# Sheet1.net
KiCad netlist of a schematic drawn in Altium Designer
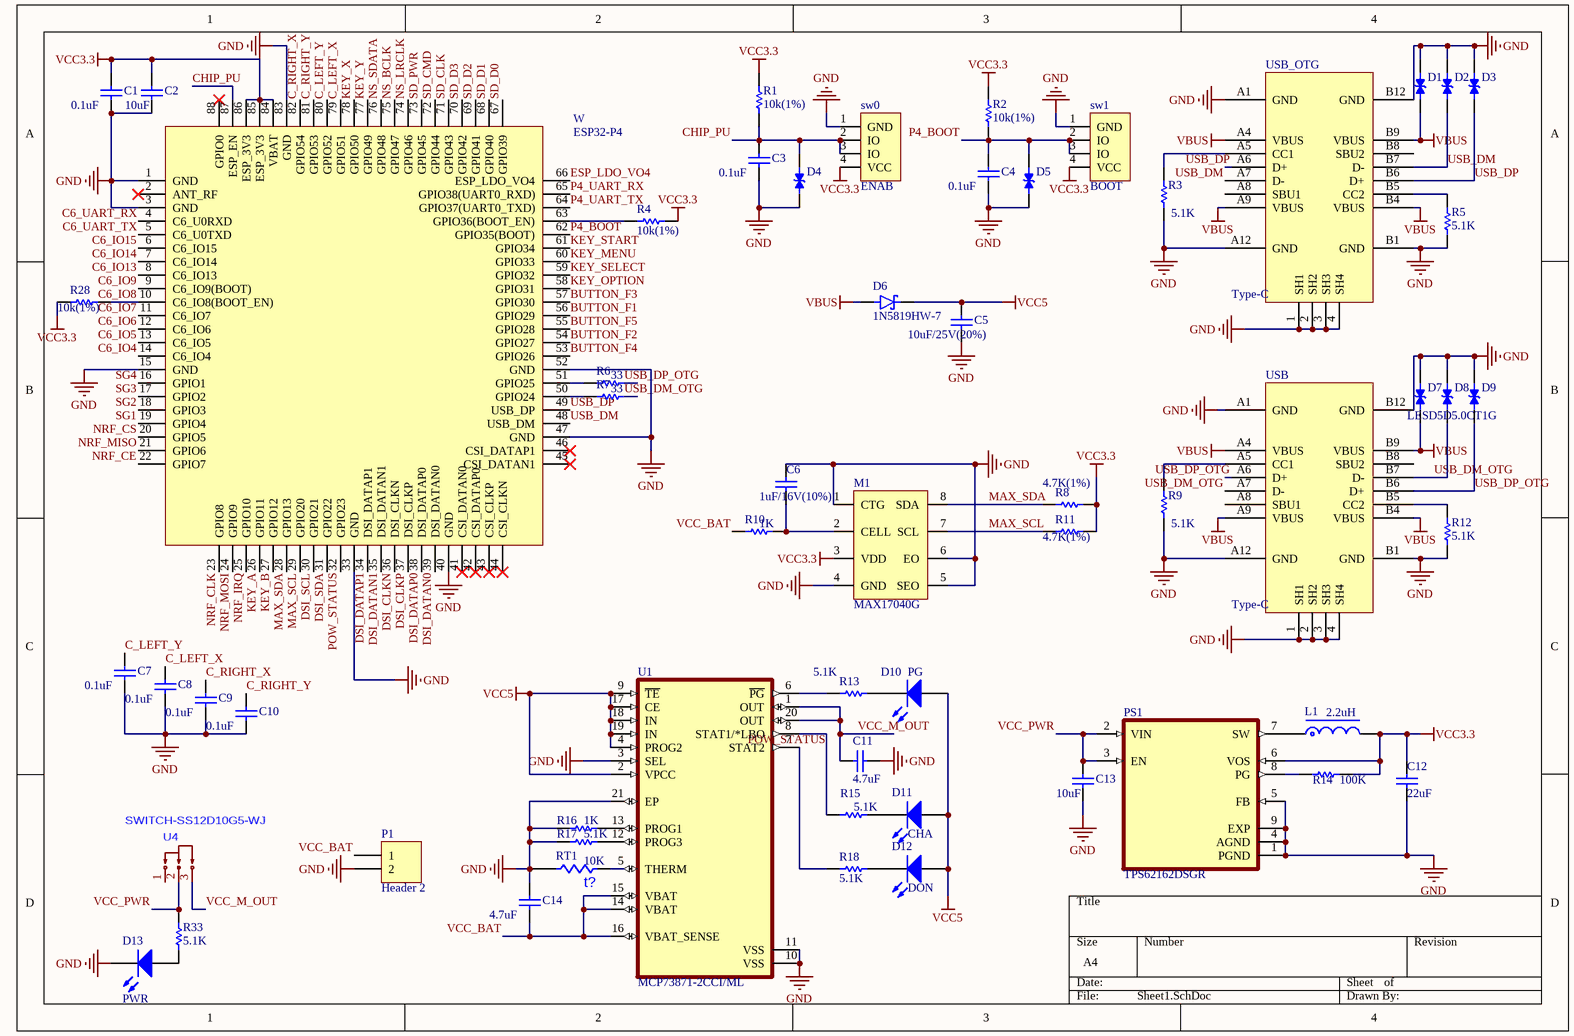
[diagram p0: Sheet1.SchDoc]

(export (version "E")
  (design (tool "Eeschema 10.0.6"))
  (components
    (comp (ref "C1")
      (value "0.1uF")
      (footprint "C0805")
      (description "Capacitor")
      (fields (field (name "Comment") "0.1uF/50V(10%)") (field (name "PUBLISHER") "Altium Limited"))
      (libsource (lib "Miscellaneous Devices") (part "Cap"))
    )
    (comp (ref "C2")
      (value "10uF")
      (footprint "C0805")
      (description "Capacitor")
      (fields (field (name "PUBLISHER") "Altium Limited"))
      (libsource (lib "Miscellaneous Devices") (part "Cap"))
    )
    (comp (ref "C3")
      (value "0.1uF")
      (footprint "C0805")
      (description "Capacitor")
      (fields (field (name "Comment") "0.1uF/50V(10%)") (field (name "PUBLISHER") "Altium Limited"))
      (libsource (lib "Miscellaneous Devices") (part "Cap"))
    )
    (comp (ref "C4")
      (value "0.1uF")
      (footprint "C0805")
      (description "Capacitor")
      (fields (field (name "Comment") "0.1uF/50V(10%)") (field (name "PUBLISHER") "Altium Limited"))
      (libsource (lib "Miscellaneous Devices") (part "Cap"))
    )
    (comp (ref "C5")
      (value "10uF/25V(20%)")
      (footprint "C0805")
      (description "Capacitor")
      (fields (field (name "PUBLISHER") "Altium Limited"))
      (libsource (lib "Miscellaneous Devices") (part "Cap"))
    )
    (comp (ref "C6")
      (value "1uF/16V(10%)")
      (footprint "C0805")
      (description "Capacitor")
      (fields (field (name "PUBLISHER") "Altium Limited"))
      (libsource (lib "Miscellaneous Devices") (part "Cap"))
    )
    (comp (ref "C7")
      (value "0.1uF")
      (footprint "C0805")
      (description "Capacitor")
      (fields (field (name "Comment") "0.1uF/50V(10%)") (field (name "PUBLISHER") "Altium Limited"))
      (libsource (lib "Miscellaneous Devices") (part "Cap"))
    )
    (comp (ref "C8")
      (value "0.1uF")
      (footprint "C0805")
      (description "Capacitor")
      (fields (field (name "Comment") "0.1uF/50V(10%)") (field (name "PUBLISHER") "Altium Limited"))
      (libsource (lib "Miscellaneous Devices") (part "Cap"))
    )
    (comp (ref "C9")
      (value "0.1uF")
      (footprint "C0805")
      (description "Capacitor")
      (fields (field (name "Comment") "0.1uF/50V(10%)") (field (name "PUBLISHER") "Altium Limited"))
      (libsource (lib "Miscellaneous Devices") (part "Cap"))
    )
    (comp (ref "C10")
      (value "0.1uF")
      (footprint "C0805")
      (description "Capacitor")
      (fields (field (name "Comment") "0.1uF/50V(10%)") (field (name "PUBLISHER") "Altium Limited"))
      (libsource (lib "Miscellaneous Devices") (part "Cap"))
    )
    (comp (ref "C11")
      (value "4.7uF")
      (footprint "C0805")
      (description "Capacitor")
      (fields (field (name "PUBLISHER") "Altium Limited"))
      (libsource (lib "Miscellaneous Devices") (part "Cap"))
    )
    (comp (ref "C12")
      (value "22uF")
      (footprint "C0805")
      (description "Capacitor")
      (fields (field (name "PUBLISHER") "Altium Limited"))
      (libsource (lib "Miscellaneous Devices") (part "Cap"))
    )
    (comp (ref "C13")
      (value "10uF")
      (footprint "C0805")
      (description "Capacitor")
      (fields (field (name "PUBLISHER") "Altium Limited"))
      (libsource (lib "Miscellaneous Devices") (part "Cap"))
    )
    (comp (ref "C14")
      (value "4.7uF")
      (footprint "C0805")
      (description "Capacitor")
      (fields (field (name "PUBLISHER") "Altium Limited"))
      (libsource (lib "Miscellaneous Devices") (part "Cap"))
    )
    (comp (ref "D1")
      (value "~")
      (footprint "TVS_LESD5D5.0CT1G")
      (description "Transient Voltage Suppressors for ESD Protection")
      (fields (field (name "MF") "Leshan Radio Co.") (field (name "MP") "LESD5D5.0CT1G"))
      (libsource (lib "welkin_lib_v1.0") (part "LESD5D5.0CT1G"))
    )
    (comp (ref "D2")
      (value "~")
      (footprint "TVS_LESD5D5.0CT1G")
      (description "Transient Voltage Suppressors for ESD Protection")
      (fields (field (name "MF") "Leshan Radio Co.") (field (name "MP") "LESD5D5.0CT1G"))
      (libsource (lib "welkin_lib_v1.0") (part "LESD5D5.0CT1G"))
    )
    (comp (ref "D3")
      (value "~")
      (footprint "TVS_LESD5D5.0CT1G")
      (description "Transient Voltage Suppressors for ESD Protection")
      (fields (field (name "MF") "Leshan Radio Co.") (field (name "MP") "LESD5D5.0CT1G"))
      (libsource (lib "welkin_lib_v1.0") (part "LESD5D5.0CT1G"))
    )
    (comp (ref "D4")
      (value "~")
      (footprint "TVS_LESD5D5.0CT1G")
      (description "Transient Voltage Suppressors for ESD Protection")
      (fields (field (name "MF") "Leshan Radio Co.") (field (name "MP") "LESD5D5.0CT1G"))
      (libsource (lib "welkin_lib_v1.0") (part "LESD5D5.0CT1G"))
    )
    (comp (ref "D5")
      (value "~")
      (footprint "TVS_LESD5D5.0CT1G")
      (description "Transient Voltage Suppressors for ESD Protection")
      (fields (field (name "MF") "Leshan Radio Co.") (field (name "MP") "LESD5D5.0CT1G"))
      (libsource (lib "welkin_lib_v1.0") (part "LESD5D5.0CT1G"))
    )
    (comp (ref "D6")
      (value "1N5819HW-7")
      (footprint "SOD3715X145N")
      (description "Diode Schottky 40 V 1A Surface Mount SOD-123")
      (fields (field (name "MF") "Diodes Inc."))
      (libsource (lib "Schlib1") (part "1N5819HW-7"))
    )
    (comp (ref "D7")
      (value "~")
      (footprint "TVS_LESD5D5.0CT1G")
      (description "Transient Voltage Suppressors for ESD Protection")
      (fields (field (name "MF") "Leshan Radio Co.") (field (name "MP") "LESD5D5.0CT1G"))
      (libsource (lib "welkin_lib_v1.0") (part "LESD5D5.0CT1G"))
    )
    (comp (ref "D8")
      (value "LESD5D5.0CT1G")
      (footprint "TVS_LESD5D5.0CT1G")
      (description "Transient Voltage Suppressors for ESD Protection")
      (fields (field (name "MF") "Leshan Radio Co."))
      (libsource (lib "welkin_lib_v1.0") (part "LESD5D5.0CT1G"))
    )
    (comp (ref "D9")
      (value "~")
      (footprint "TVS_LESD5D5.0CT1G")
      (description "Transient Voltage Suppressors for ESD Protection")
      (fields (field (name "MF") "Leshan Radio Co.") (field (name "MP") "LESD5D5.0CT1G"))
      (libsource (lib "welkin_lib_v1.0") (part "LESD5D5.0CT1G"))
    )
    (comp (ref "D10")
      (value "PG")
      (footprint "C0805")
      (description "Typical INFRARED GaAs LED")
      (fields (field (name "PUBLISHER") "Altium Limited"))
      (libsource (lib "Miscellaneous Devices") (part "LED0"))
    )
    (comp (ref "D11")
      (value "CHA")
      (footprint "C0805")
      (description "Typical INFRARED GaAs LED")
      (fields (field (name "PUBLISHER") "Altium Limited"))
      (libsource (lib "Miscellaneous Devices") (part "LED0"))
    )
    (comp (ref "D12")
      (value "DON")
      (footprint "C0805")
      (description "Typical INFRARED GaAs LED")
      (fields (field (name "PUBLISHER") "Altium Limited"))
      (libsource (lib "Miscellaneous Devices") (part "LED0"))
    )
    (comp (ref "D13")
      (value "PWR")
      (footprint "C0805")
      (description "Typical INFRARED GaAs LED")
      (fields (field (name "PUBLISHER") "Altium Limited"))
      (libsource (lib "Miscellaneous Devices") (part "LED0"))
    )
    (comp (ref "L1")
      (value "2.2uH")
      (footprint "INDC6060X300")
      (description "NR功率电感")
      (fields (field (name "版权归属") "源创客"))
      (libsource (lib "welkin_lib_v1.0") (part "L-NR"))
    )
    (comp (ref "M1")
      (value "MAX17040G")
      (footprint "MAX17040G+T")
      (description "电量检测")
      (libsource (lib "Schlib1") (part "MAX17040G"))
    )
    (comp (ref "P1")
      (value "Header 2")
      (footprint "XH2.54-2P")
      (description "Header, 2-Pin")
      (fields (field (name "PUBLISHER") "Altium Limited"))
      (libsource (lib "Miscellaneous Connectors") (part "Header 2"))
    )
    (comp (ref "PS1")
      (value "TPS62162DSGR")
      (footprint "TPS62162DSGR")
      (description "3V-17V 1A Step-Down Converters with DCS-Controlâ„¢")
      (fields (field (name "MF") "Texas Instruments"))
      (libsource (lib "welkin_lib_v1.0") (part "TPS62162DSGR"))
    )
    (comp (ref "R1")
      (value "10k(1%)")
      (footprint "C0805")
      (description "Resistor")
      (fields (field (name "PUBLISHER") "Altium Limited"))
      (libsource (lib "Miscellaneous Devices") (part "Res1"))
    )
    (comp (ref "R2")
      (value "10k(1%)")
      (footprint "C0805")
      (description "Resistor")
      (fields (field (name "PUBLISHER") "Altium Limited"))
      (libsource (lib "Miscellaneous Devices") (part "Res1"))
    )
    (comp (ref "R3")
      (value "5.1K")
      (footprint "C0805")
      (description "Resistor")
      (fields (field (name "PUBLISHER") "Altium Limited"))
      (libsource (lib "Miscellaneous Devices") (part "Res1"))
    )
    (comp (ref "R4")
      (value "10k(1%)")
      (footprint "C0805")
      (description "Resistor")
      (fields (field (name "PUBLISHER") "Altium Limited"))
      (libsource (lib "Miscellaneous Devices") (part "Res1"))
    )
    (comp (ref "R5")
      (value "5.1K")
      (footprint "C0805")
      (description "Resistor")
      (fields (field (name "PUBLISHER") "Altium Limited"))
      (libsource (lib "Miscellaneous Devices") (part "Res1"))
    )
    (comp (ref "R6")
      (value "33")
      (footprint "C0805")
      (description "Resistor")
      (fields (field (name "PUBLISHER") "Altium Limited"))
      (libsource (lib "Miscellaneous Devices") (part "Res1"))
    )
    (comp (ref "R7")
      (value "33")
      (footprint "C0805")
      (description "Resistor")
      (fields (field (name "PUBLISHER") "Altium Limited"))
      (libsource (lib "Miscellaneous Devices") (part "Res1"))
    )
    (comp (ref "R8")
      (value "4.7K(1%)")
      (footprint "C0805")
      (description "Resistor")
      (fields (field (name "PUBLISHER") "Altium Limited"))
      (libsource (lib "Miscellaneous Devices") (part "Res1"))
    )
    (comp (ref "R9")
      (value "5.1K")
      (footprint "C0805")
      (description "Resistor")
      (fields (field (name "PUBLISHER") "Altium Limited"))
      (libsource (lib "Miscellaneous Devices") (part "Res1"))
    )
    (comp (ref "R10")
      (value "1K")
      (footprint "C0805")
      (description "Resistor")
      (fields (field (name "PUBLISHER") "Altium Limited"))
      (libsource (lib "Miscellaneous Devices") (part "Res1"))
    )
    (comp (ref "R11")
      (value "4.7K(1%)")
      (footprint "C0805")
      (description "Resistor")
      (fields (field (name "PUBLISHER") "Altium Limited"))
      (libsource (lib "Miscellaneous Devices") (part "Res1"))
    )
    (comp (ref "R12")
      (value "5.1K")
      (footprint "C0805")
      (description "Resistor")
      (fields (field (name "PUBLISHER") "Altium Limited"))
      (libsource (lib "Miscellaneous Devices") (part "Res1"))
    )
    (comp (ref "R13")
      (value "5.1K")
      (footprint "C0805")
      (description "Resistor")
      (fields (field (name "PUBLISHER") "Altium Limited"))
      (libsource (lib "Miscellaneous Devices") (part "Res1"))
    )
    (comp (ref "R14")
      (value "100K")
      (footprint "C0805")
      (description "Resistor")
      (fields (field (name "PUBLISHER") "Altium Limited"))
      (libsource (lib "Miscellaneous Devices") (part "Res1"))
    )
    (comp (ref "R15")
      (value "5.1K")
      (footprint "C0805")
      (description "Resistor")
      (fields (field (name "PUBLISHER") "Altium Limited"))
      (libsource (lib "Miscellaneous Devices") (part "Res1"))
    )
    (comp (ref "R16")
      (value "1K")
      (footprint "C0805")
      (description "Resistor")
      (fields (field (name "PUBLISHER") "Altium Limited"))
      (libsource (lib "Miscellaneous Devices") (part "Res1"))
    )
    (comp (ref "R17")
      (value "5.1K")
      (footprint "C0805")
      (description "Resistor")
      (fields (field (name "PUBLISHER") "Altium Limited"))
      (libsource (lib "Miscellaneous Devices") (part "Res1"))
    )
    (comp (ref "R18")
      (value "5.1K")
      (footprint "C0805")
      (description "Resistor")
      (fields (field (name "PUBLISHER") "Altium Limited"))
      (libsource (lib "Miscellaneous Devices") (part "Res1"))
    )
    (comp (ref "R28")
      (value "10k(1%)")
      (footprint "C0805")
      (description "Resistor")
      (fields (field (name "PUBLISHER") "Altium Limited"))
      (libsource (lib "Miscellaneous Devices") (part "Res1"))
    )
    (comp (ref "R33")
      (value "5.1K")
      (footprint "C0805")
      (description "Resistor")
      (fields (field (name "PUBLISHER") "Altium Limited"))
      (libsource (lib "Miscellaneous Devices") (part "Res1"))
    )
    (comp (ref "RT1")
      (value "10K")
      (footprint "NTC")
      (fields (field (name "PUBLISHER") "Altium Limited"))
      (libsource (lib "Miscellaneous Devices") (part "Res Thermal"))
    )
    (comp (ref "sw0")
      (value "ENAB")
      (footprint "SWITH_Light")
      (libsource (lib "welkin_lib_v1.0") (part "SWITCH_LIGHT"))
    )
    (comp (ref "sw1")
      (value "BOOT")
      (footprint "SWITH_Light")
      (libsource (lib "welkin_lib_v1.0") (part "SWITCH_LIGHT"))
    )
    (comp (ref "U1")
      (value "MCP73871-2CCI/ML")
      (footprint "MCP73871")
      (description "Charger IC Lithium Ion/Polymer 20-QFN (4x4)")
      (fields (field (name "MF") "Microchip Technology"))
      (libsource (lib "welkin_lib_v1.0") (part "MCP73871-2CCI/ML"))
    )
    (comp (ref "U4")
      (value "SWITCH-SS12D10G5-WJ")
      (footprint "SW-TH_SS12D10G5")
      (libsource (lib "welkin_lib_v1.0") (part "SWITCH-SS12D10G5-WJ"))
    )
    (comp (ref "USB")
      (value "Type-C")
      (footprint "Type-C-TOP")
      (libsource (lib "Schlib1") (part "USB-Type-C-TOP"))
    )
    (comp (ref "USB_OTG")
      (value "Type-C")
      (footprint "Type-C-TOP")
      (libsource (lib "Schlib1") (part "USB-Type-C-TOP"))
    )
    (comp (ref "W")
      (value "ESP32-P4")
      (footprint "ESP32-P4_MODULE")
      (description "ESP32P4+ESP32C6")
      (libsource (lib "welkin_lib_v1.0") (part "ESP32-P4-Module"))
    )
  )
  (nets
    (net (code "1") (name "/BUTTON_F1") (class "Default")
      (node (ref "W") (pin "56") (pinfunction "GPIO29_56") (pintype "passive"))
    )
    (net (code "2") (name "/BUTTON_F2") (class "Default")
      (node (ref "W") (pin "54") (pinfunction "GPIO27_54") (pintype "passive"))
    )
    (net (code "3") (name "/BUTTON_F3") (class "Default")
      (node (ref "W") (pin "57") (pinfunction "GPIO30_57") (pintype "passive"))
    )
    (net (code "4") (name "/BUTTON_F4") (class "Default")
      (node (ref "W") (pin "53") (pinfunction "GPIO26_53") (pintype "passive"))
    )
    (net (code "5") (name "/BUTTON_F5") (class "Default")
      (node (ref "W") (pin "55") (pinfunction "GPIO28_55") (pintype "passive"))
    )
    (net (code "6") (name "/C6_IO4") (class "Default")
      (node (ref "W") (pin "14") (pinfunction "C6_IO4_14") (pintype "passive"))
    )
    (net (code "7") (name "/C6_IO5") (class "Default")
      (node (ref "W") (pin "13") (pinfunction "C6_IO5_13") (pintype "passive"))
    )
    (net (code "8") (name "/C6_IO6") (class "Default")
      (node (ref "W") (pin "12") (pinfunction "C6_IO6_12") (pintype "passive"))
    )
    (net (code "9") (name "/C6_IO7") (class "Default")
      (node (ref "W") (pin "11") (pinfunction "C6_IO7_11") (pintype "passive"))
    )
    (net (code "10") (name "/C6_IO8") (class "Default")
      (node (ref "R28") (pin "1") (pinfunction "1_1") (pintype "passive"))
      (node (ref "W") (pin "10") (pinfunction "C6_IO8(BOOT_EN)_10") (pintype "passive"))
    )
    (net (code "11") (name "/C6_IO9") (class "Default")
      (node (ref "W") (pin "9") (pinfunction "C6_IO9(BOOT)_9") (pintype "passive"))
    )
    (net (code "12") (name "/C6_IO13") (class "Default")
      (node (ref "W") (pin "8") (pinfunction "C6_IO13_8") (pintype "passive"))
    )
    (net (code "13") (name "/C6_IO14") (class "Default")
      (node (ref "W") (pin "7") (pinfunction "C6_IO14_7") (pintype "passive"))
    )
    (net (code "14") (name "/C6_IO15") (class "Default")
      (node (ref "W") (pin "6") (pinfunction "C6_IO15_6") (pintype "passive"))
    )
    (net (code "15") (name "/C6_UART_RX") (class "Default")
      (node (ref "W") (pin "4") (pinfunction "C6_U0RXD_4") (pintype "passive"))
    )
    (net (code "16") (name "/C6_UART_TX") (class "Default")
      (node (ref "W") (pin "5") (pinfunction "C6_U0TXD_5") (pintype "passive"))
    )
    (net (code "17") (name "/CHIP_PU") (class "Default")
      (node (ref "C3") (pin "2") (pinfunction "2_2") (pintype "passive"))
      (node (ref "D4") (pin "2") (pinfunction "2_2") (pintype "passive"))
      (node (ref "R1") (pin "1") (pinfunction "1_1") (pintype "passive"))
      (node (ref "W") (pin "87") (pinfunction "ESP_EN_87") (pintype "passive"))
      (node (ref "sw0") (pin "2") (pinfunction "IO_2") (pintype "passive"))
      (node (ref "sw0") (pin "3") (pinfunction "IO_3") (pintype "passive"))
    )
    (net (code "18") (name "/C_LEFT_X") (class "Default")
      (node (ref "C8") (pin "2") (pinfunction "2_2") (pintype "passive"))
      (node (ref "W") (pin "79") (pinfunction "GPIO51_79") (pintype "passive"))
    )
    (net (code "19") (name "/C_LEFT_Y") (class "Default")
      (node (ref "C7") (pin "2") (pinfunction "2_2") (pintype "passive"))
      (node (ref "W") (pin "80") (pinfunction "GPIO52_80") (pintype "passive"))
    )
    (net (code "20") (name "/C_RIGHT_X") (class "Default")
      (node (ref "C9") (pin "2") (pinfunction "2_2") (pintype "passive"))
      (node (ref "W") (pin "82") (pinfunction "GPIO54_82") (pintype "passive"))
    )
    (net (code "21") (name "/C_RIGHT_Y") (class "Default")
      (node (ref "C10") (pin "2") (pinfunction "2_2") (pintype "passive"))
      (node (ref "W") (pin "81") (pinfunction "GPIO53_81") (pintype "passive"))
    )
    (net (code "22") (name "/DSI_CLKN") (class "Default")
      (node (ref "W") (pin "36") (pinfunction "DSI_CLKN_36") (pintype "passive"))
    )
    (net (code "23") (name "/DSI_CLKP") (class "Default")
      (node (ref "W") (pin "37") (pinfunction "DSI_CLKP_37") (pintype "passive"))
    )
    (net (code "24") (name "/DSI_DATAN0") (class "Default")
      (node (ref "W") (pin "39") (pinfunction "DSI_DATAN0_39") (pintype "passive"))
    )
    (net (code "25") (name "/DSI_DATAN1") (class "Default")
      (node (ref "W") (pin "35") (pinfunction "DSI_DATAN1_35") (pintype "passive"))
    )
    (net (code "26") (name "/DSI_DATAP0") (class "Default")
      (node (ref "W") (pin "38") (pinfunction "DSI_DATAP0_38") (pintype "passive"))
    )
    (net (code "27") (name "/DSI_DATAP1") (class "Default")
      (node (ref "W") (pin "34") (pinfunction "DSI_DATAP1_34") (pintype "passive"))
    )
    (net (code "28") (name "/DSI_SCL") (class "Default")
      (node (ref "W") (pin "30") (pinfunction "GPIO21_30") (pintype "passive"))
    )
    (net (code "29") (name "/DSI_SDA") (class "Default")
      (node (ref "W") (pin "31") (pinfunction "GPIO22_31") (pintype "passive"))
    )
    (net (code "30") (name "/ESP_LDO_VO4") (class "Default")
      (node (ref "W") (pin "66") (pinfunction "ESP_LDO_VO4_66") (pintype "passive"))
    )
    (net (code "31") (name "/KEY_A") (class "Default")
      (node (ref "W") (pin "26") (pinfunction "GPIO11_26") (pintype "passive"))
    )
    (net (code "32") (name "/KEY_B") (class "Default")
      (node (ref "W") (pin "27") (pinfunction "GPIO12_27") (pintype "passive"))
    )
    (net (code "33") (name "/KEY_MENU") (class "Default")
      (node (ref "W") (pin "60") (pinfunction "GPIO33_60") (pintype "passive"))
    )
    (net (code "34") (name "/KEY_OPTION") (class "Default")
      (node (ref "W") (pin "58") (pinfunction "GPIO31_58") (pintype "passive"))
    )
    (net (code "35") (name "/KEY_SELECT") (class "Default")
      (node (ref "W") (pin "59") (pinfunction "GPIO32_59") (pintype "passive"))
    )
    (net (code "36") (name "/KEY_START") (class "Default")
      (node (ref "W") (pin "61") (pinfunction "GPIO34_61") (pintype "passive"))
    )
    (net (code "37") (name "/KEY_X") (class "Default")
      (node (ref "W") (pin "78") (pinfunction "GPIO50_78") (pintype "passive"))
    )
    (net (code "38") (name "/KEY_Y") (class "Default")
      (node (ref "W") (pin "77") (pinfunction "GPIO49_77") (pintype "passive"))
    )
    (net (code "39") (name "/MAX_SCL") (class "Default")
      (node (ref "M1") (pin "7") (pinfunction "SCL_7") (pintype "passive"))
      (node (ref "R11") (pin "1") (pinfunction "1_1") (pintype "passive"))
      (node (ref "W") (pin "29") (pinfunction "GPIO20_29") (pintype "passive"))
    )
    (net (code "40") (name "/MAX_SDA") (class "Default")
      (node (ref "M1") (pin "8") (pinfunction "SDA_8") (pintype "passive"))
      (node (ref "R8") (pin "1") (pinfunction "1_1") (pintype "passive"))
      (node (ref "W") (pin "28") (pinfunction "GPIO13_28") (pintype "passive"))
    )
    (net (code "41") (name "/NRF_CE") (class "Default")
      (node (ref "W") (pin "22") (pinfunction "GPIO7_22") (pintype "passive"))
    )
    (net (code "42") (name "/NRF_CLK") (class "Default")
      (node (ref "W") (pin "23") (pinfunction "GPIO8_23") (pintype "passive"))
    )
    (net (code "43") (name "/NRF_CS") (class "Default")
      (node (ref "W") (pin "20") (pinfunction "GPIO5_20") (pintype "passive"))
    )
    (net (code "44") (name "/NRF_IRQ") (class "Default")
      (node (ref "W") (pin "25") (pinfunction "GPIO10_25") (pintype "passive"))
    )
    (net (code "45") (name "/NRF_MISO") (class "Default")
      (node (ref "W") (pin "21") (pinfunction "GPIO6_21") (pintype "passive"))
    )
    (net (code "46") (name "/NRF_MOSI") (class "Default")
      (node (ref "W") (pin "24") (pinfunction "GPIO9_24") (pintype "passive"))
    )
    (net (code "47") (name "/NS_BCLK") (class "Default")
      (node (ref "W") (pin "75") (pinfunction "GPIO47_75") (pintype "passive"))
    )
    (net (code "48") (name "/NS_LRCLK") (class "Default")
      (node (ref "W") (pin "74") (pinfunction "GPIO46_74") (pintype "passive"))
    )
    (net (code "49") (name "/NS_SDATA") (class "Default")
      (node (ref "W") (pin "76") (pinfunction "GPIO48_76") (pintype "passive"))
    )
    (net (code "50") (name "/P4_BOOT") (class "Default")
      (node (ref "C4") (pin "2") (pinfunction "2_2") (pintype "passive"))
      (node (ref "D5") (pin "2") (pinfunction "2_2") (pintype "passive"))
      (node (ref "R2") (pin "1") (pinfunction "1_1") (pintype "passive"))
      (node (ref "W") (pin "62") (pinfunction "GPIO35(BOOT)_62") (pintype "passive"))
      (node (ref "sw1") (pin "2") (pinfunction "IO_2") (pintype "passive"))
      (node (ref "sw1") (pin "3") (pinfunction "IO_3") (pintype "passive"))
    )
    (net (code "51") (name "/P4_UART_RX") (class "Default")
      (node (ref "W") (pin "65") (pinfunction "GPIO38(UART0_RXD)_65") (pintype "passive"))
    )
    (net (code "52") (name "/P4_UART_TX") (class "Default")
      (node (ref "W") (pin "64") (pinfunction "GPIO37(UART0_TXD)_64") (pintype "passive"))
    )
    (net (code "53") (name "/POW_STATUS") (class "Default")
      (node (ref "R15") (pin "2") (pinfunction "2_2") (pintype "passive"))
      (node (ref "U1") (pin "8") (pinfunction "STAT1/*LBO_8") (pintype "output"))
      (node (ref "W") (pin "32") (pinfunction "GPIO23_32") (pintype "passive"))
    )
    (net (code "54") (name "/SD_CLK") (class "Default")
      (node (ref "W") (pin "71") (pinfunction "GPIO43_71") (pintype "passive"))
    )
    (net (code "55") (name "/SD_CMD") (class "Default")
      (node (ref "W") (pin "72") (pinfunction "GPIO44_72") (pintype "passive"))
    )
    (net (code "56") (name "/SD_D0") (class "Default")
      (node (ref "W") (pin "67") (pinfunction "GPIO39_67") (pintype "passive"))
    )
    (net (code "57") (name "/SD_D1") (class "Default")
      (node (ref "W") (pin "68") (pinfunction "GPIO40_68") (pintype "passive"))
    )
    (net (code "58") (name "/SD_D2") (class "Default")
      (node (ref "W") (pin "69") (pinfunction "GPIO41_69") (pintype "passive"))
    )
    (net (code "59") (name "/SD_D3") (class "Default")
      (node (ref "W") (pin "70") (pinfunction "GPIO42_70") (pintype "passive"))
    )
    (net (code "60") (name "/SD_PWR") (class "Default")
      (node (ref "W") (pin "73") (pinfunction "GPIO45_73") (pintype "passive"))
    )
    (net (code "61") (name "/SG1") (class "Default")
      (node (ref "W") (pin "19") (pinfunction "GPIO4_19") (pintype "passive"))
    )
    (net (code "62") (name "/SG2") (class "Default")
      (node (ref "W") (pin "18") (pinfunction "GPIO3_18") (pintype "passive"))
    )
    (net (code "63") (name "/SG3") (class "Default")
      (node (ref "W") (pin "17") (pinfunction "GPIO2_17") (pintype "passive"))
    )
    (net (code "64") (name "/SG4") (class "Default")
      (node (ref "W") (pin "16") (pinfunction "GPIO1_16") (pintype "passive"))
    )
    (net (code "65") (name "/USB_DM") (class "Default")
      (node (ref "D2") (pin "1") (pinfunction "1_1") (pintype "passive"))
      (node (ref "USB_OTG") (pin "A7") (pinfunction "D-_A7") (pintype "passive"))
      (node (ref "USB_OTG") (pin "B7") (pinfunction "D-_B7") (pintype "passive"))
      (node (ref "W") (pin "48") (pinfunction "USB_DM_48") (pintype "passive"))
    )
    (net (code "66") (name "/USB_DM_OTG") (class "Default")
      (node (ref "D8") (pin "1") (pinfunction "1_1") (pintype "passive"))
      (node (ref "R7") (pin "1") (pinfunction "1_1") (pintype "passive"))
      (node (ref "USB") (pin "A7") (pinfunction "D-_A7") (pintype "passive"))
      (node (ref "USB") (pin "B7") (pinfunction "D-_B7") (pintype "passive"))
    )
    (net (code "67") (name "/USB_DP") (class "Default")
      (node (ref "D3") (pin "1") (pinfunction "1_1") (pintype "passive"))
      (node (ref "USB_OTG") (pin "A6") (pinfunction "D+_A6") (pintype "passive"))
      (node (ref "USB_OTG") (pin "B6") (pinfunction "D+_B6") (pintype "passive"))
      (node (ref "W") (pin "49") (pinfunction "USB_DP_49") (pintype "passive"))
    )
    (net (code "68") (name "/USB_DP_OTG") (class "Default")
      (node (ref "D9") (pin "1") (pinfunction "1_1") (pintype "passive"))
      (node (ref "R6") (pin "1") (pinfunction "1_1") (pintype "passive"))
      (node (ref "USB") (pin "A6") (pinfunction "D+_A6") (pintype "passive"))
      (node (ref "USB") (pin "B6") (pinfunction "D+_B6") (pintype "passive"))
    )
    (net (code "69") (name "/VCC_BAT") (class "Default")
      (node (ref "C14") (pin "1") (pinfunction "1_1") (pintype "passive"))
      (node (ref "P1") (pin "1") (pinfunction "1_1") (pintype "passive"))
      (node (ref "R10") (pin "1") (pinfunction "1_1") (pintype "passive"))
      (node (ref "U1") (pin "14") (pinfunction "VBAT_14") (pintype "bidirectional"))
      (node (ref "U1") (pin "15") (pinfunction "VBAT_15") (pintype "bidirectional"))
      (node (ref "U1") (pin "16") (pinfunction "VBAT_SENSE_16") (pintype "bidirectional"))
    )
    (net (code "70") (name "/VCC_M_OUT") (class "Default")
      (node (ref "C11") (pin "1") (pinfunction "1_1") (pintype "passive"))
      (node (ref "U1") (pin "1") (pinfunction "OUT_1") (pintype "bidirectional"))
      (node (ref "U1") (pin "20") (pinfunction "OUT_20") (pintype "bidirectional"))
      (node (ref "U4") (pin "3") (pinfunction "3_3") (pintype "passive"))
    )
    (net (code "71") (name "/VCC_PWR") (class "Default")
      (node (ref "C13") (pin "2") (pinfunction "2_2") (pintype "passive"))
      (node (ref "PS1") (pin "2") (pinfunction "VIN_2") (pintype "input"))
      (node (ref "PS1") (pin "3") (pinfunction "EN_3") (pintype "input"))
      (node (ref "R33") (pin "1") (pinfunction "1_1") (pintype "passive"))
      (node (ref "U4") (pin "2") (pinfunction "2_2") (pintype "passive"))
    )
    (net (code "72") (name "GND") (class "Default")
      (node (ref "C1") (pin "1") (pinfunction "1_1") (pintype "passive"))
      (node (ref "C10") (pin "1") (pinfunction "1_1") (pintype "passive"))
      (node (ref "C11") (pin "2") (pinfunction "2_2") (pintype "passive"))
      (node (ref "C12") (pin "1") (pinfunction "1_1") (pintype "passive"))
      (node (ref "C13") (pin "1") (pinfunction "1_1") (pintype "passive"))
      (node (ref "C14") (pin "2") (pinfunction "2_2") (pintype "passive"))
      (node (ref "C2") (pin "1") (pinfunction "1_1") (pintype "passive"))
      (node (ref "C3") (pin "1") (pinfunction "1_1") (pintype "passive"))
      (node (ref "C4") (pin "1") (pinfunction "1_1") (pintype "passive"))
      (node (ref "C5") (pin "1") (pinfunction "1_1") (pintype "passive"))
      (node (ref "C6") (pin "2") (pinfunction "2_2") (pintype "passive"))
      (node (ref "C7") (pin "1") (pinfunction "1_1") (pintype "passive"))
      (node (ref "C8") (pin "1") (pinfunction "1_1") (pintype "passive"))
      (node (ref "C9") (pin "1") (pinfunction "1_1") (pintype "passive"))
      (node (ref "D1") (pin "2") (pinfunction "2_2") (pintype "passive"))
      (node (ref "D13") (pin "2") (pinfunction "K_2") (pintype "passive"))
      (node (ref "D2") (pin "2") (pinfunction "2_2") (pintype "passive"))
      (node (ref "D3") (pin "2") (pinfunction "2_2") (pintype "passive"))
      (node (ref "D4") (pin "1") (pinfunction "1_1") (pintype "passive"))
      (node (ref "D5") (pin "1") (pinfunction "1_1") (pintype "passive"))
      (node (ref "D7") (pin "2") (pinfunction "2_2") (pintype "passive"))
      (node (ref "D8") (pin "2") (pinfunction "2_2") (pintype "passive"))
      (node (ref "D9") (pin "2") (pinfunction "2_2") (pintype "passive"))
      (node (ref "M1") (pin "1") (pinfunction "CTG_1") (pintype "passive"))
      (node (ref "M1") (pin "4") (pinfunction "GND_4") (pintype "passive"))
      (node (ref "M1") (pin "5") (pinfunction "SEO_5") (pintype "passive"))
      (node (ref "M1") (pin "6") (pinfunction "EO_6") (pintype "passive"))
      (node (ref "P1") (pin "2") (pinfunction "2_2") (pintype "passive"))
      (node (ref "PS1") (pin "1") (pinfunction "PGND_1") (pintype "power_in"))
      (node (ref "PS1") (pin "4") (pinfunction "AGND_4") (pintype "power_in"))
      (node (ref "PS1") (pin "5") (pinfunction "FB_5") (pintype "input"))
      (node (ref "PS1") (pin "9") (pinfunction "EXP_9") (pintype "passive"))
      (node (ref "R12") (pin "1") (pinfunction "1_1") (pintype "passive"))
      (node (ref "R16") (pin "2") (pinfunction "2_2") (pintype "passive"))
      (node (ref "R17") (pin "2") (pinfunction "2_2") (pintype "passive"))
      (node (ref "R3") (pin "1") (pinfunction "1_1") (pintype "passive"))
      (node (ref "R5") (pin "1") (pinfunction "1_1") (pintype "passive"))
      (node (ref "R9") (pin "1") (pinfunction "1_1") (pintype "passive"))
      (node (ref "RT1") (pin "2") (pinfunction "2_2") (pintype "passive"))
      (node (ref "U1") (pin "10") (pinfunction "VSS_10") (pintype "power_in"))
      (node (ref "U1") (pin "11") (pinfunction "VSS_11") (pintype "power_in"))
      (node (ref "U1") (pin "21") (pinfunction "EP_21") (pintype "bidirectional"))
      (node (ref "U1") (pin "3") (pinfunction "SEL_3") (pintype "input"))
      (node (ref "USB") (pin "1") (pinfunction "SH1_1") (pintype "passive"))
      (node (ref "USB") (pin "2") (pinfunction "SH2_2") (pintype "passive"))
      (node (ref "USB") (pin "3") (pinfunction "SH3_3") (pintype "passive"))
      (node (ref "USB") (pin "4") (pinfunction "SH4_4") (pintype "passive"))
      (node (ref "USB") (pin "A1") (pinfunction "GND_A1") (pintype "passive"))
      (node (ref "USB") (pin "A12") (pinfunction "GND_A12") (pintype "passive"))
      (node (ref "USB") (pin "B1") (pinfunction "GND_B1") (pintype "passive"))
      (node (ref "USB") (pin "B12") (pinfunction "GND_B12") (pintype "passive"))
      (node (ref "USB_OTG") (pin "1") (pinfunction "SH1_1") (pintype "passive"))
      (node (ref "USB_OTG") (pin "2") (pinfunction "SH2_2") (pintype "passive"))
      (node (ref "USB_OTG") (pin "3") (pinfunction "SH3_3") (pintype "passive"))
      (node (ref "USB_OTG") (pin "4") (pinfunction "SH4_4") (pintype "passive"))
      (node (ref "USB_OTG") (pin "A1") (pinfunction "GND_A1") (pintype "passive"))
      (node (ref "USB_OTG") (pin "A12") (pinfunction "GND_A12") (pintype "passive"))
      (node (ref "USB_OTG") (pin "B1") (pinfunction "GND_B1") (pintype "passive"))
      (node (ref "USB_OTG") (pin "B12") (pinfunction "GND_B12") (pintype "passive"))
      (node (ref "W") (pin "1") (pinfunction "GND_1") (pintype "passive"))
      (node (ref "W") (pin "15") (pinfunction "GND_15") (pintype "passive"))
      (node (ref "W") (pin "3") (pinfunction "GND_3") (pintype "passive"))
      (node (ref "W") (pin "33") (pinfunction "GND_33") (pintype "passive"))
      (node (ref "W") (pin "40") (pinfunction "GND_40") (pintype "passive"))
      (node (ref "W") (pin "47") (pinfunction "GND_47") (pintype "passive"))
      (node (ref "W") (pin "52") (pinfunction "GND_52") (pintype "passive"))
      (node (ref "W") (pin "83") (pinfunction "GND_83") (pintype "passive"))
      (node (ref "sw0") (pin "1") (pinfunction "GND_1") (pintype "passive"))
      (node (ref "sw1") (pin "1") (pinfunction "GND_1") (pintype "passive"))
    )
    (net (code "73") (name "Net-(D10-K)") (class "Default")
      (node (ref "D10") (pin "2") (pinfunction "K_2") (pintype "passive"))
      (node (ref "R13") (pin "1") (pinfunction "1_1") (pintype "passive"))
    )
    (net (code "74") (name "Net-(D11-K)") (class "Default")
      (node (ref "D11") (pin "2") (pinfunction "K_2") (pintype "passive"))
      (node (ref "R15") (pin "1") (pinfunction "1_1") (pintype "passive"))
    )
    (net (code "75") (name "Net-(D12-K)") (class "Default")
      (node (ref "D12") (pin "2") (pinfunction "K_2") (pintype "passive"))
      (node (ref "R18") (pin "1") (pinfunction "1_1") (pintype "passive"))
    )
    (net (code "76") (name "Net-(D13-A)") (class "Default")
      (node (ref "D13") (pin "1") (pinfunction "A_1") (pintype "passive"))
      (node (ref "R33") (pin "2") (pinfunction "2_2") (pintype "passive"))
    )
    (net (code "77") (name "Net-(M1-CELL)") (class "Default")
      (node (ref "C6") (pin "1") (pinfunction "1_1") (pintype "passive"))
      (node (ref "M1") (pin "2") (pinfunction "CELL_2") (pintype "passive"))
      (node (ref "R10") (pin "2") (pinfunction "2_2") (pintype "passive"))
    )
    (net (code "78") (name "Net-(PS1-PG)") (class "Default")
      (node (ref "PS1") (pin "8") (pinfunction "PG_8") (pintype "output"))
      (node (ref "R14") (pin "2") (pinfunction "2_2") (pintype "passive"))
    )
    (net (code "79") (name "Net-(PS1-SW)") (class "Default")
      (node (ref "L1") (pin "1") (pinfunction "1_1") (pintype "passive"))
      (node (ref "PS1") (pin "7") (pinfunction "SW_7") (pintype "output"))
    )
    (net (code "80") (name "Net-(U1-PROG1)") (class "Default")
      (node (ref "R16") (pin "1") (pinfunction "1_1") (pintype "passive"))
      (node (ref "U1") (pin "13") (pinfunction "PROG1_13") (pintype "bidirectional"))
    )
    (net (code "81") (name "Net-(U1-PROG3)") (class "Default")
      (node (ref "R17") (pin "1") (pinfunction "1_1") (pintype "passive"))
      (node (ref "U1") (pin "12") (pinfunction "PROG3_12") (pintype "bidirectional"))
    )
    (net (code "82") (name "Net-(U1-STAT2)") (class "Default")
      (node (ref "R18") (pin "2") (pinfunction "2_2") (pintype "passive"))
      (node (ref "U1") (pin "7") (pinfunction "STAT2_7") (pintype "output"))
    )
    (net (code "83") (name "Net-(U1-THERM)") (class "Default")
      (node (ref "RT1") (pin "1") (pinfunction "1_1") (pintype "passive"))
      (node (ref "U1") (pin "5") (pinfunction "THERM_5") (pintype "bidirectional"))
    )
    (net (code "84") (name "Net-(U1-~{PG})") (class "Default")
      (node (ref "R13") (pin "2") (pinfunction "2_2") (pintype "passive"))
      (node (ref "U1") (pin "6") (pinfunction "~{PG}_6") (pintype "output"))
    )
    (net (code "85") (name "Net-(USB-CC1)") (class "Default")
      (node (ref "R9") (pin "2") (pinfunction "2_2") (pintype "passive"))
      (node (ref "USB") (pin "A5") (pinfunction "CC1_A5") (pintype "passive"))
    )
    (net (code "86") (name "Net-(USB-CC2)") (class "Default")
      (node (ref "R12") (pin "2") (pinfunction "2_2") (pintype "passive"))
      (node (ref "USB") (pin "B5") (pinfunction "CC2_B5") (pintype "passive"))
    )
    (net (code "87") (name "Net-(USB_OTG-CC1)") (class "Default")
      (node (ref "R3") (pin "2") (pinfunction "2_2") (pintype "passive"))
      (node (ref "USB_OTG") (pin "A5") (pinfunction "CC1_A5") (pintype "passive"))
    )
    (net (code "88") (name "Net-(USB_OTG-CC2)") (class "Default")
      (node (ref "R5") (pin "2") (pinfunction "2_2") (pintype "passive"))
      (node (ref "USB_OTG") (pin "B5") (pinfunction "CC2_B5") (pintype "passive"))
    )
    (net (code "89") (name "Net-(W-GPIO24)") (class "Default")
      (node (ref "R7") (pin "2") (pinfunction "2_2") (pintype "passive"))
      (node (ref "W") (pin "50") (pinfunction "GPIO24_50") (pintype "passive"))
    )
    (net (code "90") (name "Net-(W-GPIO25)") (class "Default")
      (node (ref "R6") (pin "2") (pinfunction "2_2") (pintype "passive"))
      (node (ref "W") (pin "51") (pinfunction "GPIO25_51") (pintype "passive"))
    )
    (net (code "91") (name "Net-(W-GPIO36(BOOT_EN))") (class "Default")
      (node (ref "R4") (pin "1") (pinfunction "1_1") (pintype "passive"))
      (node (ref "W") (pin "63") (pinfunction "GPIO36(BOOT_EN)_63") (pintype "passive"))
    )
    (net (code "92") (name "VBUS") (class "Default")
      (node (ref "D1") (pin "1") (pinfunction "1_1") (pintype "passive"))
      (node (ref "D6") (pin "A") (pinfunction "A_A") (pintype "passive"))
      (node (ref "D7") (pin "1") (pinfunction "1_1") (pintype "passive"))
      (node (ref "USB") (pin "A4") (pinfunction "VBUS_A4") (pintype "passive"))
      (node (ref "USB") (pin "A9") (pinfunction "VBUS_A9") (pintype "passive"))
      (node (ref "USB") (pin "B4") (pinfunction "VBUS_B4") (pintype "passive"))
      (node (ref "USB") (pin "B9") (pinfunction "VBUS_B9") (pintype "passive"))
      (node (ref "USB_OTG") (pin "A4") (pinfunction "VBUS_A4") (pintype "passive"))
      (node (ref "USB_OTG") (pin "A9") (pinfunction "VBUS_A9") (pintype "passive"))
      (node (ref "USB_OTG") (pin "B4") (pinfunction "VBUS_B4") (pintype "passive"))
      (node (ref "USB_OTG") (pin "B9") (pinfunction "VBUS_B9") (pintype "passive"))
    )
    (net (code "93") (name "VCC3.3") (class "Default")
      (node (ref "C1") (pin "2") (pinfunction "2_2") (pintype "passive"))
      (node (ref "C12") (pin "2") (pinfunction "2_2") (pintype "passive"))
      (node (ref "C2") (pin "2") (pinfunction "2_2") (pintype "passive"))
      (node (ref "L1") (pin "2") (pinfunction "2_2") (pintype "passive"))
      (node (ref "M1") (pin "3") (pinfunction "VDD_3") (pintype "passive"))
      (node (ref "PS1") (pin "6") (pinfunction "VOS_6") (pintype "input"))
      (node (ref "R1") (pin "2") (pinfunction "2_2") (pintype "passive"))
      (node (ref "R11") (pin "2") (pinfunction "2_2") (pintype "passive"))
      (node (ref "R14") (pin "1") (pinfunction "1_1") (pintype "passive"))
      (node (ref "R2") (pin "2") (pinfunction "2_2") (pintype "passive"))
      (node (ref "R28") (pin "2") (pinfunction "2_2") (pintype "passive"))
      (node (ref "R4") (pin "2") (pinfunction "2_2") (pintype "passive"))
      (node (ref "R8") (pin "2") (pinfunction "2_2") (pintype "passive"))
      (node (ref "W") (pin "84") (pinfunction "VBAT_84") (pintype "passive"))
      (node (ref "W") (pin "85") (pinfunction "ESP_3V3_85") (pintype "passive"))
      (node (ref "W") (pin "86") (pinfunction "ESP_3V3_86") (pintype "passive"))
      (node (ref "sw0") (pin "4") (pinfunction "VCC_4") (pintype "passive"))
      (node (ref "sw1") (pin "4") (pinfunction "VCC_4") (pintype "passive"))
    )
    (net (code "94") (name "VCC5") (class "Default")
      (node (ref "C5") (pin "2") (pinfunction "2_2") (pintype "passive"))
      (node (ref "D10") (pin "1") (pinfunction "A_1") (pintype "passive"))
      (node (ref "D11") (pin "1") (pinfunction "A_1") (pintype "passive"))
      (node (ref "D12") (pin "1") (pinfunction "A_1") (pintype "passive"))
      (node (ref "D6") (pin "C") (pinfunction "K_C") (pintype "passive"))
      (node (ref "U1") (pin "17") (pinfunction "CE_17") (pintype "input"))
      (node (ref "U1") (pin "18") (pinfunction "IN_18") (pintype "input"))
      (node (ref "U1") (pin "19") (pinfunction "IN_19") (pintype "input"))
      (node (ref "U1") (pin "2") (pinfunction "VPCC_2") (pintype "input"))
      (node (ref "U1") (pin "4") (pinfunction "PROG2_4") (pintype "input"))
      (node (ref "U1") (pin "9") (pinfunction "~{TE}_9") (pintype "input"))
    )
    (net (code "95") (name "unconnected-(U4-Pad1)") (class "Default")
      (node (ref "U4") (pin "1") (pinfunction "1_1") (pintype "passive"))
    )
    (net (code "96") (name "unconnected-(USB-SBU1-PadA8)") (class "Default")
      (node (ref "USB") (pin "A8") (pinfunction "SBU1_A8") (pintype "passive"))
    )
    (net (code "97") (name "unconnected-(USB-SBU2-PadB8)") (class "Default")
      (node (ref "USB") (pin "B8") (pinfunction "SBU2_B8") (pintype "passive"))
    )
    (net (code "98") (name "unconnected-(USB_OTG-SBU1-PadA8)") (class "Default")
      (node (ref "USB_OTG") (pin "A8") (pinfunction "SBU1_A8") (pintype "passive"))
    )
    (net (code "99") (name "unconnected-(USB_OTG-SBU2-PadB8)") (class "Default")
      (node (ref "USB_OTG") (pin "B8") (pinfunction "SBU2_B8") (pintype "passive"))
    )
    (net (code "100") (name "unconnected-(W-ANT_RF-Pad2)") (class "Default")
      (node (ref "W") (pin "2") (pinfunction "ANT_RF_2") (pintype "passive+no_connect"))
    )
    (net (code "101") (name "unconnected-(W-CSI_CLKN-Pad44)") (class "Default")
      (node (ref "W") (pin "44") (pinfunction "CSI_CLKN_44") (pintype "passive+no_connect"))
    )
    (net (code "102") (name "unconnected-(W-CSI_CLKP-Pad43)") (class "Default")
      (node (ref "W") (pin "43") (pinfunction "CSI_CLKP_43") (pintype "passive+no_connect"))
    )
    (net (code "103") (name "unconnected-(W-CSI_DATAN0-Pad41)") (class "Default")
      (node (ref "W") (pin "41") (pinfunction "CSI_DATAN0_41") (pintype "passive+no_connect"))
    )
    (net (code "104") (name "unconnected-(W-CSI_DATAN1-Pad45)") (class "Default")
      (node (ref "W") (pin "45") (pinfunction "CSI_DATAN1_45") (pintype "passive+no_connect"))
    )
    (net (code "105") (name "unconnected-(W-CSI_DATAP0-Pad42)") (class "Default")
      (node (ref "W") (pin "42") (pinfunction "CSI_DATAP0_42") (pintype "passive+no_connect"))
    )
    (net (code "106") (name "unconnected-(W-CSI_DATAP1-Pad46)") (class "Default")
      (node (ref "W") (pin "46") (pinfunction "CSI_DATAP1_46") (pintype "passive+no_connect"))
    )
    (net (code "107") (name "unconnected-(W-GPIO0-Pad88)") (class "Default")
      (node (ref "W") (pin "88") (pinfunction "GPIO0_88") (pintype "passive+no_connect"))
    )
  )
)
